# VUSB_Protoboard.net
KiCad netlist of a schematic drawn in EAGLE
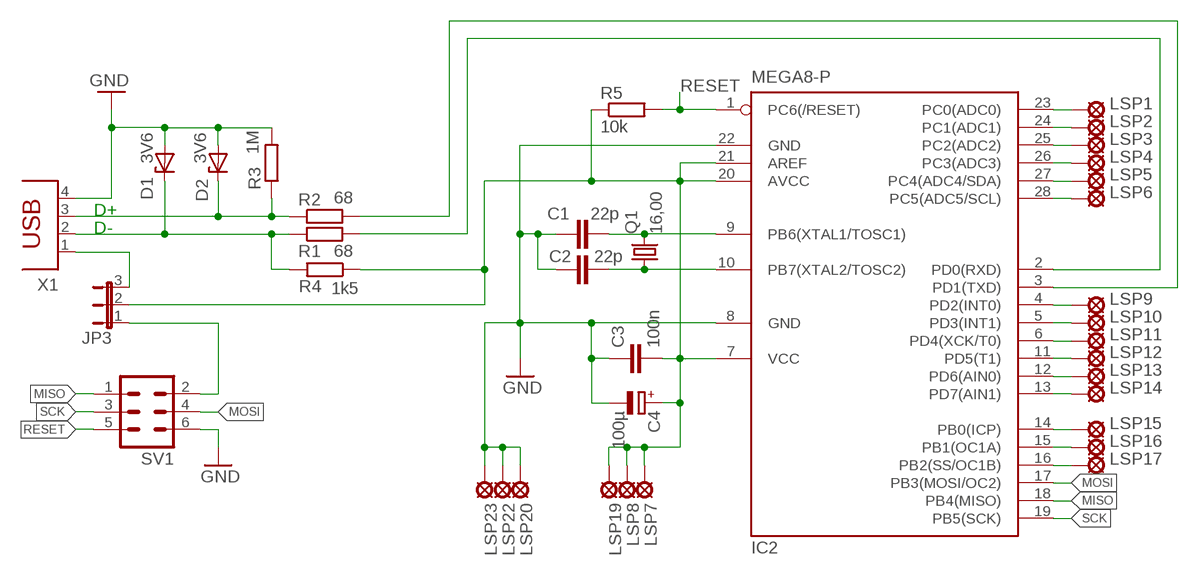
[diagram p0: schematic, sheet 1]

(export (version "E")
  (design (tool "Eeschema 10.0.6"))
  (components
    (comp (ref "C1")
      (value "22p")
      (footprint "eagle-import:C025-025X050")
      (libsource (lib "eagle-import") (part "C-EU025-025X050"))
    )
    (comp (ref "C2")
      (value "22p")
      (footprint "eagle-import:C025-025X050")
      (libsource (lib "eagle-import") (part "C-EU025-025X050"))
    )
    (comp (ref "C3")
      (value "100n")
      (footprint "eagle-import:C025-025X050")
      (libsource (lib "eagle-import") (part "C-EU025-025X050"))
    )
    (comp (ref "C4")
      (value "100µ")
      (footprint "eagle-import:E2,5-6")
      (libsource (lib "eagle-import") (part "CPOL-EUE2.5-6"))
    )
    (comp (ref "D1")
      (value "3V6")
      (footprint "eagle-import:ZDIO-7.5")
      (libsource (lib "eagle-import") (part "ZENER-DIODEZD-7.5"))
    )
    (comp (ref "D2")
      (value "3V6")
      (footprint "eagle-import:ZDIO-7.5")
      (libsource (lib "eagle-import") (part "ZENER-DIODEZD-7.5"))
    )
    (comp (ref "IC2")
      (value "MEGA8-P")
      (footprint "eagle-import:DIL28-3")
      (libsource (lib "eagle-import") (part "MEGA8-P"))
    )
    (comp (ref "JP3")
      (value "JP2E")
      (footprint "eagle-import:JP2")
      (libsource (lib "eagle-import") (part "JP2E"))
    )
    (comp (ref "LSP1")
      (value "LSP11")
      (footprint "eagle-import:LSP11")
      (libsource (lib "eagle-import") (part "LSP11"))
    )
    (comp (ref "LSP2")
      (value "LSP11")
      (footprint "eagle-import:LSP11")
      (libsource (lib "eagle-import") (part "LSP11"))
    )
    (comp (ref "LSP3")
      (value "LSP11")
      (footprint "eagle-import:LSP11")
      (libsource (lib "eagle-import") (part "LSP11"))
    )
    (comp (ref "LSP4")
      (value "LSP11")
      (footprint "eagle-import:LSP11")
      (libsource (lib "eagle-import") (part "LSP11"))
    )
    (comp (ref "LSP5")
      (value "LSP11")
      (footprint "eagle-import:LSP11")
      (libsource (lib "eagle-import") (part "LSP11"))
    )
    (comp (ref "LSP6")
      (value "LSP11")
      (footprint "eagle-import:LSP11")
      (libsource (lib "eagle-import") (part "LSP11"))
    )
    (comp (ref "LSP7")
      (value "LSP11")
      (footprint "eagle-import:LSP11")
      (libsource (lib "eagle-import") (part "LSP11"))
    )
    (comp (ref "LSP8")
      (value "LSP11")
      (footprint "eagle-import:LSP11")
      (libsource (lib "eagle-import") (part "LSP11"))
    )
    (comp (ref "LSP9")
      (value "LSP11")
      (footprint "eagle-import:LSP11")
      (libsource (lib "eagle-import") (part "LSP11"))
    )
    (comp (ref "LSP10")
      (value "LSP11")
      (footprint "eagle-import:LSP11")
      (libsource (lib "eagle-import") (part "LSP11"))
    )
    (comp (ref "LSP11")
      (value "LSP11")
      (footprint "eagle-import:LSP11")
      (libsource (lib "eagle-import") (part "LSP11"))
    )
    (comp (ref "LSP12")
      (value "LSP11")
      (footprint "eagle-import:LSP11")
      (libsource (lib "eagle-import") (part "LSP11"))
    )
    (comp (ref "LSP13")
      (value "LSP11")
      (footprint "eagle-import:LSP11")
      (libsource (lib "eagle-import") (part "LSP11"))
    )
    (comp (ref "LSP14")
      (value "LSP11")
      (footprint "eagle-import:LSP11")
      (libsource (lib "eagle-import") (part "LSP11"))
    )
    (comp (ref "LSP15")
      (value "LSP11")
      (footprint "eagle-import:LSP11")
      (libsource (lib "eagle-import") (part "LSP11"))
    )
    (comp (ref "LSP16")
      (value "LSP11")
      (footprint "eagle-import:LSP11")
      (libsource (lib "eagle-import") (part "LSP11"))
    )
    (comp (ref "LSP17")
      (value "LSP11")
      (footprint "eagle-import:LSP11")
      (libsource (lib "eagle-import") (part "LSP11"))
    )
    (comp (ref "LSP19")
      (value "LSP11")
      (footprint "eagle-import:LSP11")
      (libsource (lib "eagle-import") (part "LSP11"))
    )
    (comp (ref "LSP20")
      (value "LSP11")
      (footprint "eagle-import:LSP11")
      (libsource (lib "eagle-import") (part "LSP11"))
    )
    (comp (ref "LSP22")
      (value "LSP11")
      (footprint "eagle-import:LSP11")
      (libsource (lib "eagle-import") (part "LSP11"))
    )
    (comp (ref "LSP23")
      (value "LSP11")
      (footprint "eagle-import:LSP11")
      (libsource (lib "eagle-import") (part "LSP11"))
    )
    (comp (ref "Q1")
      (value "16,00")
      (footprint "eagle-import:HC49_S")
      (libsource (lib "eagle-import") (part "CRYSTALHC49S"))
    )
    (comp (ref "R1")
      (value "68")
      (footprint "eagle-import:0207_10")
      (libsource (lib "eagle-import") (part "R-EU_0207/10"))
    )
    (comp (ref "R2")
      (value "68")
      (footprint "eagle-import:0207_10")
      (libsource (lib "eagle-import") (part "R-EU_0207/10"))
    )
    (comp (ref "R3")
      (value "1M")
      (footprint "eagle-import:0207_10")
      (libsource (lib "eagle-import") (part "R-EU_0207/10"))
    )
    (comp (ref "R4")
      (value "1k5")
      (footprint "eagle-import:0207_10")
      (libsource (lib "eagle-import") (part "R-EU_0207/10"))
    )
    (comp (ref "R5")
      (value "10k")
      (footprint "eagle-import:0207_10")
      (libsource (lib "eagle-import") (part "R-EU_0207/10"))
    )
    (comp (ref "SV1")
      (value "ML6")
      (footprint "eagle-import:ML6")
      (libsource (lib "eagle-import") (part "ML6"))
    )
    (comp (ref "X1")
      (value "PN61729")
      (footprint "eagle-import:PN61729")
      (libsource (lib "eagle-import") (part "PN61729"))
    )
  )
  (nets
    (net (code "1") (name "GND") (class "Default")
      (node (ref "C1") (pin "1") (pinfunction "1_1") (pintype "passive"))
      (node (ref "C2") (pin "1") (pinfunction "1_1") (pintype "passive"))
      (node (ref "C3") (pin "1") (pinfunction "1_1") (pintype "passive"))
      (node (ref "C4") (pin "-") (pinfunction "-_-") (pintype "passive"))
      (node (ref "D1") (pin "A") (pinfunction "A_A") (pintype "passive"))
      (node (ref "D2") (pin "A") (pinfunction "A_A") (pintype "passive"))
      (node (ref "IC2") (pin "22") (pinfunction "GND_22") (pintype "power_in"))
      (node (ref "IC2") (pin "8") (pinfunction "GND_8") (pintype "power_in"))
      (node (ref "LSP20") (pin "MP") (pinfunction "MP_MP") (pintype "passive"))
      (node (ref "LSP22") (pin "MP") (pinfunction "MP_MP") (pintype "passive"))
      (node (ref "LSP23") (pin "MP") (pinfunction "MP_MP") (pintype "passive"))
      (node (ref "R3") (pin "2") (pinfunction "2_2") (pintype "passive"))
      (node (ref "SV1") (pin "6") (pinfunction "6_6") (pintype "passive"))
      (node (ref "X1") (pin "4") (pinfunction "4_4") (pintype "passive"))
    )
    (net (code "2") (name "MISO") (class "Default")
      (node (ref "IC2") (pin "18") (pinfunction "PB4(MISO)_18") (pintype "bidirectional"))
      (node (ref "SV1") (pin "1") (pinfunction "1_1") (pintype "passive"))
    )
    (net (code "3") (name "MOSI") (class "Default")
      (node (ref "IC2") (pin "17") (pinfunction "PB3(MOSI/OC2)_17") (pintype "bidirectional"))
      (node (ref "SV1") (pin "4") (pinfunction "4_4") (pintype "passive"))
    )
    (net (code "4") (name "Net-(D1-PadC)") (class "Default")
      (node (ref "D1") (pin "C") (pinfunction "C_C") (pintype "passive"))
      (node (ref "R1") (pin "1") (pinfunction "1_1") (pintype "passive"))
      (node (ref "R4") (pin "2") (pinfunction "2_2") (pintype "passive"))
      (node (ref "X1") (pin "2") (pinfunction "2_2") (pintype "passive"))
    )
    (net (code "5") (name "Net-(D2-PadC)") (class "Default")
      (node (ref "D2") (pin "C") (pinfunction "C_C") (pintype "passive"))
      (node (ref "R2") (pin "1") (pinfunction "1_1") (pintype "passive"))
      (node (ref "R3") (pin "1") (pinfunction "1_1") (pintype "passive"))
      (node (ref "X1") (pin "3") (pinfunction "3_3") (pintype "passive"))
    )
    (net (code "6") (name "Net-(IC2-AREF)") (class "Default")
      (node (ref "C3") (pin "2") (pinfunction "2_2") (pintype "passive"))
      (node (ref "C4") (pin "+") (pinfunction "+_+") (pintype "passive"))
      (node (ref "IC2") (pin "20") (pinfunction "AVCC_20") (pintype "power_in"))
      (node (ref "IC2") (pin "21") (pinfunction "AREF_21") (pintype "passive"))
      (node (ref "IC2") (pin "7") (pinfunction "VCC_7") (pintype "power_in"))
      (node (ref "JP3") (pin "2") (pinfunction "2_2") (pintype "passive"))
      (node (ref "LSP19") (pin "MP") (pinfunction "MP_MP") (pintype "passive"))
      (node (ref "LSP7") (pin "MP") (pinfunction "MP_MP") (pintype "passive"))
      (node (ref "LSP8") (pin "MP") (pinfunction "MP_MP") (pintype "passive"))
      (node (ref "R4") (pin "1") (pinfunction "1_1") (pintype "passive"))
      (node (ref "R5") (pin "1") (pinfunction "1_1") (pintype "passive"))
    )
    (net (code "7") (name "Net-(IC2-PB0(ICP))") (class "Default")
      (node (ref "IC2") (pin "14") (pinfunction "PB0(ICP)_14") (pintype "bidirectional"))
      (node (ref "LSP15") (pin "MP") (pinfunction "MP_MP") (pintype "passive"))
    )
    (net (code "8") (name "Net-(IC2-PB1(OC1A))") (class "Default")
      (node (ref "IC2") (pin "15") (pinfunction "PB1(OC1A)_15") (pintype "bidirectional"))
      (node (ref "LSP16") (pin "MP") (pinfunction "MP_MP") (pintype "passive"))
    )
    (net (code "9") (name "Net-(IC2-PB2(SS{slash}OC1B))") (class "Default")
      (node (ref "IC2") (pin "16") (pinfunction "PB2(SS/OC1B)_16") (pintype "bidirectional"))
      (node (ref "LSP17") (pin "MP") (pinfunction "MP_MP") (pintype "passive"))
    )
    (net (code "10") (name "Net-(IC2-PB6(XTAL1{slash}TOSC1))") (class "Default")
      (node (ref "C1") (pin "2") (pinfunction "2_2") (pintype "passive"))
      (node (ref "IC2") (pin "9") (pinfunction "PB6(XTAL1/TOSC1)_9") (pintype "bidirectional"))
      (node (ref "Q1") (pin "2") (pinfunction "2_2") (pintype "passive"))
    )
    (net (code "11") (name "Net-(IC2-PB7(XTAL2{slash}TOSC2))") (class "Default")
      (node (ref "C2") (pin "2") (pinfunction "2_2") (pintype "passive"))
      (node (ref "IC2") (pin "10") (pinfunction "PB7(XTAL2/TOSC2)_10") (pintype "bidirectional"))
      (node (ref "Q1") (pin "1") (pinfunction "1_1") (pintype "passive"))
    )
    (net (code "12") (name "Net-(IC2-PC0(ADC0))") (class "Default")
      (node (ref "IC2") (pin "23") (pinfunction "PC0(ADC0)_23") (pintype "bidirectional"))
      (node (ref "LSP1") (pin "MP") (pinfunction "MP_MP") (pintype "passive"))
    )
    (net (code "13") (name "Net-(IC2-PC1(ADC1))") (class "Default")
      (node (ref "IC2") (pin "24") (pinfunction "PC1(ADC1)_24") (pintype "bidirectional"))
      (node (ref "LSP2") (pin "MP") (pinfunction "MP_MP") (pintype "passive"))
    )
    (net (code "14") (name "Net-(IC2-PC2(ADC2))") (class "Default")
      (node (ref "IC2") (pin "25") (pinfunction "PC2(ADC2)_25") (pintype "bidirectional"))
      (node (ref "LSP3") (pin "MP") (pinfunction "MP_MP") (pintype "passive"))
    )
    (net (code "15") (name "Net-(IC2-PC3(ADC3))") (class "Default")
      (node (ref "IC2") (pin "26") (pinfunction "PC3(ADC3)_26") (pintype "bidirectional"))
      (node (ref "LSP4") (pin "MP") (pinfunction "MP_MP") (pintype "passive"))
    )
    (net (code "16") (name "Net-(IC2-PC4(ADC4{slash}SDA))") (class "Default")
      (node (ref "IC2") (pin "27") (pinfunction "PC4(ADC4/SDA)_27") (pintype "bidirectional"))
      (node (ref "LSP5") (pin "MP") (pinfunction "MP_MP") (pintype "passive"))
    )
    (net (code "17") (name "Net-(IC2-PC5(ADC5{slash}SCL))") (class "Default")
      (node (ref "IC2") (pin "28") (pinfunction "PC5(ADC5/SCL)_28") (pintype "bidirectional"))
      (node (ref "LSP6") (pin "MP") (pinfunction "MP_MP") (pintype "passive"))
    )
    (net (code "18") (name "Net-(IC2-PD0(RXD))") (class "Default")
      (node (ref "IC2") (pin "2") (pinfunction "PD0(RXD)_2") (pintype "bidirectional"))
      (node (ref "R1") (pin "2") (pinfunction "2_2") (pintype "passive"))
    )
    (net (code "19") (name "Net-(IC2-PD1(TXD))") (class "Default")
      (node (ref "IC2") (pin "3") (pinfunction "PD1(TXD)_3") (pintype "bidirectional"))
      (node (ref "R2") (pin "2") (pinfunction "2_2") (pintype "passive"))
    )
    (net (code "20") (name "Net-(IC2-PD2(INT0))") (class "Default")
      (node (ref "IC2") (pin "4") (pinfunction "PD2(INT0)_4") (pintype "bidirectional"))
      (node (ref "LSP9") (pin "MP") (pinfunction "MP_MP") (pintype "passive"))
    )
    (net (code "21") (name "Net-(IC2-PD3(INT1))") (class "Default")
      (node (ref "IC2") (pin "5") (pinfunction "PD3(INT1)_5") (pintype "bidirectional"))
      (node (ref "LSP10") (pin "MP") (pinfunction "MP_MP") (pintype "passive"))
    )
    (net (code "22") (name "Net-(IC2-PD4(XCK{slash}T0))") (class "Default")
      (node (ref "IC2") (pin "6") (pinfunction "PD4(XCK/T0)_6") (pintype "bidirectional"))
      (node (ref "LSP11") (pin "MP") (pinfunction "MP_MP") (pintype "passive"))
    )
    (net (code "23") (name "Net-(IC2-PD5(T1))") (class "Default")
      (node (ref "IC2") (pin "11") (pinfunction "PD5(T1)_11") (pintype "bidirectional"))
      (node (ref "LSP12") (pin "MP") (pinfunction "MP_MP") (pintype "passive"))
    )
    (net (code "24") (name "Net-(IC2-PD6(AIN0))") (class "Default")
      (node (ref "IC2") (pin "12") (pinfunction "PD6(AIN0)_12") (pintype "bidirectional"))
      (node (ref "LSP13") (pin "MP") (pinfunction "MP_MP") (pintype "passive"))
    )
    (net (code "25") (name "Net-(IC2-PD7(AIN1))") (class "Default")
      (node (ref "IC2") (pin "13") (pinfunction "PD7(AIN1)_13") (pintype "bidirectional"))
      (node (ref "LSP14") (pin "MP") (pinfunction "MP_MP") (pintype "passive"))
    )
    (net (code "26") (name "Net-(JP3-Pad1)") (class "Default")
      (node (ref "JP3") (pin "1") (pinfunction "1_1") (pintype "passive"))
      (node (ref "SV1") (pin "2") (pinfunction "2_2") (pintype "passive"))
    )
    (net (code "27") (name "Net-(JP3-Pad3)") (class "Default")
      (node (ref "JP3") (pin "3") (pinfunction "3_3") (pintype "passive"))
      (node (ref "X1") (pin "1") (pinfunction "1_1") (pintype "passive"))
    )
    (net (code "28") (name "RESET") (class "Default")
      (node (ref "IC2") (pin "1") (pinfunction "PC6(/RESET)_1") (pintype "bidirectional"))
      (node (ref "R5") (pin "2") (pinfunction "2_2") (pintype "passive"))
      (node (ref "SV1") (pin "5") (pinfunction "5_5") (pintype "passive"))
    )
    (net (code "29") (name "SCK") (class "Default")
      (node (ref "IC2") (pin "19") (pinfunction "PB5(SCK)_19") (pintype "bidirectional"))
      (node (ref "SV1") (pin "3") (pinfunction "3_3") (pintype "passive"))
    )
  )
)
